# wemosd1pro-bme280.net
KiCad netlist of a schematic drawn in EAGLE
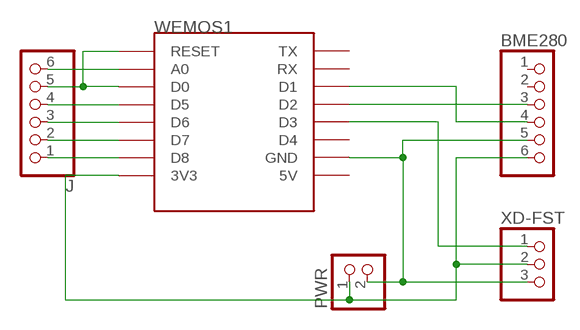
[diagram p0: schematic, sheet 1]

(export (version "E")
  (design (tool "Eeschema 10.0.6"))
  (components
    (comp (ref "BME280")
      (value "PINHD-1X6")
      (footprint "eagle-import:1X06")
      (libsource (lib "eagle-import") (part "PINHD-1X6"))
    )
    (comp (ref "J")
      (value "PINHD-1X6")
      (footprint "eagle-import:1X06")
      (libsource (lib "eagle-import") (part "PINHD-1X6"))
    )
    (comp (ref "PWR")
      (value "PINHD-1X2")
      (footprint "eagle-import:1X02")
      (libsource (lib "eagle-import") (part "PINHD-1X2"))
    )
    (comp (ref "WEMOS1")
      (value "WEMOS-D1-MINI")
      (footprint "eagle-import:WEMOS-D1-MINI")
      (libsource (lib "eagle-import") (part "WEMOS-D1-MINI"))
    )
    (comp (ref "XD-FST")
      (value "PINHD-1X3")
      (footprint "eagle-import:1X03")
      (libsource (lib "eagle-import") (part "PINHD-1X3"))
    )
  )
  (nets
    (net (code "1") (name "Net-(BME280-Pad3)") (class "Default")
      (node (ref "BME280") (pin "3") (pinfunction "3_3") (pintype "passive"))
      (node (ref "WEMOS1") (pin "D2") (pinfunction "D2_D2") (pintype "bidirectional"))
    )
    (net (code "2") (name "Net-(BME280-Pad4)") (class "Default")
      (node (ref "BME280") (pin "4") (pinfunction "4_4") (pintype "passive"))
      (node (ref "WEMOS1") (pin "D1") (pinfunction "D1_D1") (pintype "bidirectional"))
    )
    (net (code "3") (name "Net-(BME280-Pad5)") (class "Default")
      (node (ref "BME280") (pin "5") (pinfunction "5_5") (pintype "passive"))
      (node (ref "PWR") (pin "2") (pinfunction "2_2") (pintype "passive"))
      (node (ref "WEMOS1") (pin "GND") (pinfunction "GND_GND") (pintype "bidirectional"))
      (node (ref "XD-FST") (pin "3") (pinfunction "3_3") (pintype "passive"))
    )
    (net (code "4") (name "Net-(BME280-Pad6)") (class "Default")
      (node (ref "BME280") (pin "6") (pinfunction "6_6") (pintype "passive"))
      (node (ref "PWR") (pin "1") (pinfunction "1_1") (pintype "passive"))
      (node (ref "WEMOS1") (pin "3V3") (pinfunction "3V3_3V3") (pintype "bidirectional"))
      (node (ref "XD-FST") (pin "2") (pinfunction "2_2") (pintype "passive"))
    )
    (net (code "5") (name "Net-(J-Pad1)") (class "Default")
      (node (ref "J") (pin "1") (pinfunction "1_1") (pintype "passive"))
      (node (ref "WEMOS1") (pin "D8") (pinfunction "D8_D8") (pintype "bidirectional"))
    )
    (net (code "6") (name "Net-(J-Pad2)") (class "Default")
      (node (ref "J") (pin "2") (pinfunction "2_2") (pintype "passive"))
      (node (ref "WEMOS1") (pin "D7") (pinfunction "D7_D7") (pintype "bidirectional"))
    )
    (net (code "7") (name "Net-(J-Pad3)") (class "Default")
      (node (ref "J") (pin "3") (pinfunction "3_3") (pintype "passive"))
      (node (ref "WEMOS1") (pin "D6") (pinfunction "D6_D6") (pintype "bidirectional"))
    )
    (net (code "8") (name "Net-(J-Pad4)") (class "Default")
      (node (ref "J") (pin "4") (pinfunction "4_4") (pintype "passive"))
      (node (ref "WEMOS1") (pin "D5") (pinfunction "D5_D5") (pintype "bidirectional"))
    )
    (net (code "9") (name "Net-(J-Pad5)") (class "Default")
      (node (ref "J") (pin "5") (pinfunction "5_5") (pintype "passive"))
      (node (ref "WEMOS1") (pin "D0") (pinfunction "D0_D0") (pintype "bidirectional"))
      (node (ref "WEMOS1") (pin "RESET") (pinfunction "RESET_RESET") (pintype "bidirectional"))
    )
    (net (code "10") (name "Net-(J-Pad6)") (class "Default")
      (node (ref "J") (pin "6") (pinfunction "6_6") (pintype "passive"))
      (node (ref "WEMOS1") (pin "A0") (pinfunction "A0_A0") (pintype "bidirectional"))
    )
    (net (code "11") (name "Net-(WEMOS1-PadD3)") (class "Default")
      (node (ref "WEMOS1") (pin "D3") (pinfunction "D3_D3") (pintype "bidirectional"))
      (node (ref "XD-FST") (pin "1") (pinfunction "1_1") (pintype "passive"))
    )
    (net (code "12") (name "unconnected-(BME280-Pad1)") (class "Default")
      (node (ref "BME280") (pin "1") (pinfunction "1_1") (pintype "passive"))
    )
    (net (code "13") (name "unconnected-(BME280-Pad2)") (class "Default")
      (node (ref "BME280") (pin "2") (pinfunction "2_2") (pintype "passive"))
    )
    (net (code "14") (name "unconnected-(WEMOS1-Pad5V)") (class "Default")
      (node (ref "WEMOS1") (pin "5V") (pinfunction "5V_5V") (pintype "bidirectional"))
    )
    (net (code "15") (name "unconnected-(WEMOS1-PadD4)") (class "Default")
      (node (ref "WEMOS1") (pin "D4") (pinfunction "D4_D4") (pintype "bidirectional"))
    )
    (net (code "16") (name "unconnected-(WEMOS1-PadRX)") (class "Default")
      (node (ref "WEMOS1") (pin "RX") (pinfunction "RX_RX") (pintype "bidirectional"))
    )
    (net (code "17") (name "unconnected-(WEMOS1-PadTX)") (class "Default")
      (node (ref "WEMOS1") (pin "TX") (pinfunction "TX_TX") (pintype "bidirectional"))
    )
  )
)
